# interface_dac_sma.net
KiCad netlist of a schematic drawn in EAGLE
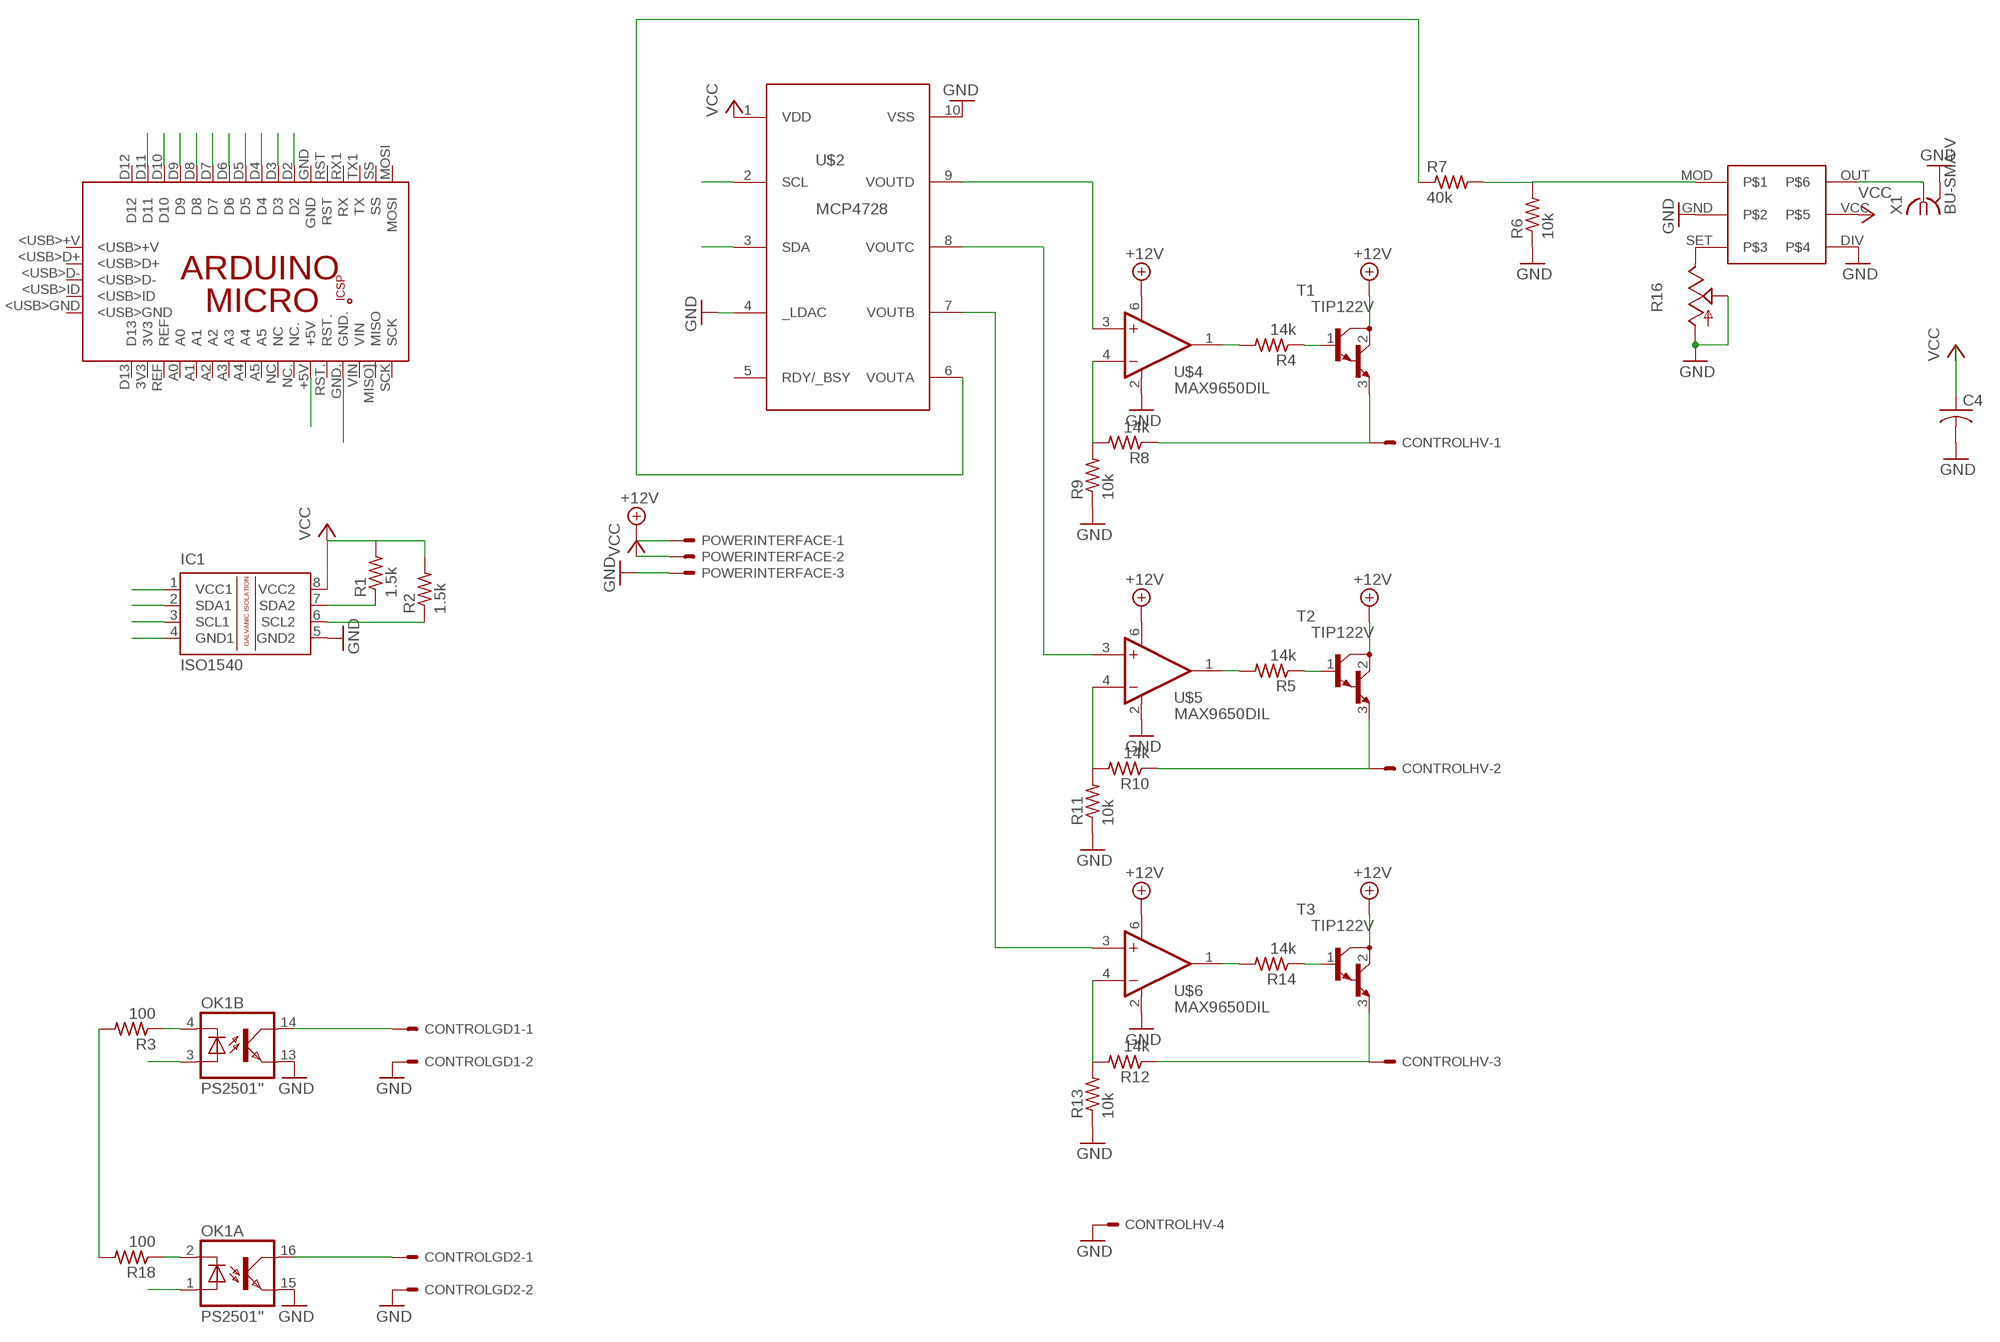
[diagram p0: schematic, sheet 1]

(export (version "E")
  (design (tool "Eeschema 10.0.6"))
  (components
    (comp (ref "C4")
      (value "C-US075-063X106")
      (footprint "eagle-import:C075-063X106")
      (libsource (lib "eagle-import") (part "C-US075-063X106"))
    )
    (comp (ref "CONTROLGD1")
      (value "KK-156-2")
      (footprint "eagle-import:KK-156-2")
      (libsource (lib "eagle-import") (part "KK-156-2"))
    )
    (comp (ref "CONTROLGD2")
      (value "KK-156-2")
      (footprint "eagle-import:KK-156-2")
      (libsource (lib "eagle-import") (part "KK-156-2"))
    )
    (comp (ref "CONTROLHV")
      (value "KK-156-4")
      (footprint "eagle-import:KK-156-4")
      (libsource (lib "eagle-import") (part "KK-156-4"))
    )
    (comp (ref "IC1")
      (value "ISO1540")
      (footprint "eagle-import:DIL08")
      (libsource (lib "eagle-import") (part "ISO1540"))
    )
    (comp (ref "OK1")
      (value "PS2501\"")
      (footprint "eagle-import:DIL16")
      (libsource (lib "eagle-import") (part "PS2501{dblquote}"))
    )
    (comp (ref "PCB1")
      (value "ARDUINO_MICRO")
      (footprint "eagle-import:ARDUINO_MICRO")
      (libsource (lib "eagle-import") (part "ARDUINO_MICRO"))
    )
    (comp (ref "POWERINTERFACE")
      (value "KK-156-3")
      (footprint "eagle-import:KK-156-3")
      (libsource (lib "eagle-import") (part "KK-156-3"))
    )
    (comp (ref "R1")
      (value "1.5k")
      (footprint "eagle-import:0207_12")
      (libsource (lib "eagle-import") (part "resistor_R-US_0207/12"))
    )
    (comp (ref "R2")
      (value "1.5k")
      (footprint "eagle-import:0207_12")
      (libsource (lib "eagle-import") (part "resistor_R-US_0207/12"))
    )
    (comp (ref "R3")
      (value "100")
      (footprint "eagle-import:0207_12")
      (libsource (lib "eagle-import") (part "R-US_0207/12"))
    )
    (comp (ref "R4")
      (value "14k")
      (footprint "eagle-import:0207_12")
      (libsource (lib "eagle-import") (part "resistor_R-US_0207/12"))
    )
    (comp (ref "R5")
      (value "14k")
      (footprint "eagle-import:0207_12")
      (libsource (lib "eagle-import") (part "resistor_R-US_0207/12"))
    )
    (comp (ref "R6")
      (value "10k")
      (footprint "eagle-import:0207_12")
      (libsource (lib "eagle-import") (part "resistor_R-US_0207/12"))
    )
    (comp (ref "R7")
      (value "40k")
      (footprint "eagle-import:0207_12")
      (libsource (lib "eagle-import") (part "resistor_R-US_0207/12"))
    )
    (comp (ref "R8")
      (value "14k")
      (footprint "eagle-import:0207_12")
      (libsource (lib "eagle-import") (part "resistor_R-US_0207/12"))
    )
    (comp (ref "R9")
      (value "10k")
      (footprint "eagle-import:0207_12")
      (libsource (lib "eagle-import") (part "resistor_R-US_0207/12"))
    )
    (comp (ref "R10")
      (value "14k")
      (footprint "eagle-import:0207_12")
      (libsource (lib "eagle-import") (part "resistor_R-US_0207/12"))
    )
    (comp (ref "R11")
      (value "10k")
      (footprint "eagle-import:0207_12")
      (libsource (lib "eagle-import") (part "resistor_R-US_0207/12"))
    )
    (comp (ref "R12")
      (value "14k")
      (footprint "eagle-import:0207_12")
      (libsource (lib "eagle-import") (part "resistor_R-US_0207/12"))
    )
    (comp (ref "R13")
      (value "10k")
      (footprint "eagle-import:0207_12")
      (libsource (lib "eagle-import") (part "resistor_R-US_0207/12"))
    )
    (comp (ref "R14")
      (value "14k")
      (footprint "eagle-import:0207_12")
      (libsource (lib "eagle-import") (part "resistor_R-US_0207/12"))
    )
    (comp (ref "R16")
      (value "TRIM_US-B90P")
      (footprint "eagle-import:SP19L")
      (libsource (lib "eagle-import") (part "TRIM_US-B90P"))
    )
    (comp (ref "R18")
      (value "100")
      (footprint "eagle-import:0207_12")
      (libsource (lib "eagle-import") (part "R-US_0207/12"))
    )
    (comp (ref "T1")
      (value "TIP122V")
      (footprint "eagle-import:TO220V")
      (libsource (lib "eagle-import") (part "TIP122V"))
    )
    (comp (ref "T2")
      (value "TIP122V")
      (footprint "eagle-import:TO220V")
      (libsource (lib "eagle-import") (part "TIP122V"))
    )
    (comp (ref "T3")
      (value "TIP122V")
      (footprint "eagle-import:TO220V")
      (libsource (lib "eagle-import") (part "TIP122V"))
    )
    (comp (ref "U$1")
      (value "LTC6992")
      (footprint "eagle-import:DIL06")
      (libsource (lib "eagle-import") (part "LTC6992"))
    )
    (comp (ref "U$2")
      (value "MCP4728DIL")
      (footprint "eagle-import:DIL10")
      (libsource (lib "eagle-import") (part "MCP4728DIL"))
    )
    (comp (ref "U$4")
      (value "MAX9650DIL")
      (footprint "eagle-import:DIL06-4")
      (libsource (lib "eagle-import") (part "MAX9650DIL"))
    )
    (comp (ref "U$5")
      (value "MAX9650DIL")
      (footprint "eagle-import:DIL06-4")
      (libsource (lib "eagle-import") (part "MAX9650DIL"))
    )
    (comp (ref "U$6")
      (value "MAX9650DIL")
      (footprint "eagle-import:DIL06-4")
      (libsource (lib "eagle-import") (part "MAX9650DIL"))
    )
    (comp (ref "X1")
      (value "BU-SMA-V")
      (footprint "eagle-import:BU-SMA-V")
      (libsource (lib "eagle-import") (part "BU-SMA-V"))
    )
  )
  (nets
    (net (code "1") (name "+12V") (class "Default")
      (node (ref "POWERINTERFACE") (pin "1") (pinfunction "S_1") (pintype "passive"))
      (node (ref "T1") (pin "2") (pinfunction "C_2") (pintype "passive"))
      (node (ref "T2") (pin "2") (pinfunction "C_2") (pintype "passive"))
      (node (ref "T3") (pin "2") (pinfunction "C_2") (pintype "passive"))
      (node (ref "U$4") (pin "6") (pinfunction "V+_6") (pintype "power_in"))
      (node (ref "U$5") (pin "6") (pinfunction "V+_6") (pintype "power_in"))
      (node (ref "U$6") (pin "6") (pinfunction "V+_6") (pintype "power_in"))
    )
    (net (code "2") (name "/A+5") (class "Default")
      (node (ref "IC1") (pin "1") (pinfunction "VCC1_1") (pintype "input"))
      (node (ref "PCB1") (pin "+5V") (pinfunction "+5V_+5V") (pintype "bidirectional"))
    )
    (net (code "3") (name "/AGND") (class "Default")
      (node (ref "IC1") (pin "4") (pinfunction "GND1_4") (pintype "input"))
      (node (ref "PCB1") (pin "GND.") (pinfunction "GND._GND.") (pintype "bidirectional"))
      (node (ref "R18") (pin "2") (pinfunction "2_2") (pintype "passive"))
      (node (ref "R3") (pin "2") (pinfunction "2_2") (pintype "passive"))
    )
    (net (code "4") (name "/N$2") (class "Default")
      (node (ref "R6") (pin "2") (pinfunction "2_2") (pintype "passive"))
      (node (ref "R7") (pin "2") (pinfunction "2_2") (pintype "passive"))
      (node (ref "U$1") (pin "MOD") (pinfunction "P$1_MOD") (pintype "bidirectional"))
    )
    (net (code "5") (name "/PWM6") (class "Default")
      (node (ref "OK1") (pin "3") (pinfunction "A_3") (pintype "passive"))
      (node (ref "PCB1") (pin "D6") (pinfunction "D6_D6") (pintype "bidirectional"))
    )
    (net (code "6") (name "/PWM9") (class "Default")
      (node (ref "OK1") (pin "1") (pinfunction "A_1") (pintype "passive"))
      (node (ref "PCB1") (pin "D9") (pinfunction "D9_D9") (pintype "bidirectional"))
    )
    (net (code "7") (name "/SCL") (class "Default")
      (node (ref "IC1") (pin "3") (pinfunction "SCL1_3") (pintype "input"))
      (node (ref "PCB1") (pin "D3") (pinfunction "D3_D3") (pintype "bidirectional"))
    )
    (net (code "8") (name "/SCL_OUT") (class "Default")
      (node (ref "IC1") (pin "6") (pinfunction "SCL2_6") (pintype "input"))
      (node (ref "R2") (pin "1") (pinfunction "1_1") (pintype "passive"))
      (node (ref "U$2") (pin "2") (pinfunction "SCL_2") (pintype "bidirectional"))
    )
    (net (code "9") (name "/SDA") (class "Default")
      (node (ref "IC1") (pin "2") (pinfunction "SDA1_2") (pintype "input"))
      (node (ref "PCB1") (pin "D2") (pinfunction "D2_D2") (pintype "bidirectional"))
    )
    (net (code "10") (name "/SDA_OUT") (class "Default")
      (node (ref "IC1") (pin "7") (pinfunction "SDA2_7") (pintype "input"))
      (node (ref "R1") (pin "1") (pinfunction "1_1") (pintype "passive"))
      (node (ref "U$2") (pin "3") (pinfunction "SDA_3") (pintype "bidirectional"))
    )
    (net (code "11") (name "GND") (class "Default")
      (node (ref "C4") (pin "2") (pinfunction "2_2") (pintype "passive"))
      (node (ref "CONTROLGD1") (pin "2") (pinfunction "S_2") (pintype "passive"))
      (node (ref "CONTROLGD2") (pin "2") (pinfunction "S_2") (pintype "passive"))
      (node (ref "CONTROLHV") (pin "4") (pinfunction "S_4") (pintype "passive"))
      (node (ref "IC1") (pin "5") (pinfunction "GND2_5") (pintype "input"))
      (node (ref "OK1") (pin "13") (pinfunction "EMI_13") (pintype "passive"))
      (node (ref "OK1") (pin "15") (pinfunction "EMI_15") (pintype "passive"))
      (node (ref "POWERINTERFACE") (pin "3") (pinfunction "S_3") (pintype "passive"))
      (node (ref "R11") (pin "1") (pinfunction "1_1") (pintype "passive"))
      (node (ref "R13") (pin "1") (pinfunction "1_1") (pintype "passive"))
      (node (ref "R16") (pin "A") (pinfunction "A_A") (pintype "passive"))
      (node (ref "R16") (pin "S") (pinfunction "S_S") (pintype "passive"))
      (node (ref "R6") (pin "1") (pinfunction "1_1") (pintype "passive"))
      (node (ref "R9") (pin "1") (pinfunction "1_1") (pintype "passive"))
      (node (ref "U$1") (pin "DIV") (pinfunction "P$4_DIV") (pintype "bidirectional"))
      (node (ref "U$1") (pin "GND") (pinfunction "P$2_GND") (pintype "bidirectional"))
      (node (ref "U$2") (pin "10") (pinfunction "VSS_10") (pintype "bidirectional"))
      (node (ref "U$2") (pin "4") (pinfunction "_LDAC_4") (pintype "bidirectional"))
      (node (ref "U$4") (pin "2") (pinfunction "V-_2") (pintype "power_in"))
      (node (ref "U$5") (pin "2") (pinfunction "V-_2") (pintype "power_in"))
      (node (ref "U$6") (pin "2") (pinfunction "V-_2") (pintype "power_in"))
      (node (ref "X1") (pin "2") (pinfunction "2_2") (pintype "passive"))
      (node (ref "X1") (pin "3") (pinfunction "2_3") (pintype "passive"))
      (node (ref "X1") (pin "4") (pinfunction "2_4") (pintype "passive"))
      (node (ref "X1") (pin "5") (pinfunction "2_5") (pintype "passive"))
    )
    (net (code "12") (name "Net-(CONTROLGD1A-S)") (class "Default")
      (node (ref "CONTROLGD1") (pin "1") (pinfunction "S_1") (pintype "passive"))
      (node (ref "OK1") (pin "14") (pinfunction "COL_14") (pintype "passive"))
    )
    (net (code "13") (name "Net-(CONTROLGD2A-S)") (class "Default")
      (node (ref "CONTROLGD2") (pin "1") (pinfunction "S_1") (pintype "passive"))
      (node (ref "OK1") (pin "16") (pinfunction "COL_16") (pintype "passive"))
    )
    (net (code "14") (name "Net-(CONTROLHVA-S)") (class "Default")
      (node (ref "CONTROLHV") (pin "1") (pinfunction "S_1") (pintype "passive"))
      (node (ref "R8") (pin "1") (pinfunction "1_1") (pintype "passive"))
      (node (ref "T1") (pin "3") (pinfunction "E_3") (pintype "passive"))
    )
    (net (code "15") (name "Net-(CONTROLHVB-S)") (class "Default")
      (node (ref "CONTROLHV") (pin "2") (pinfunction "S_2") (pintype "passive"))
      (node (ref "R10") (pin "1") (pinfunction "1_1") (pintype "passive"))
      (node (ref "T2") (pin "3") (pinfunction "E_3") (pintype "passive"))
    )
    (net (code "16") (name "Net-(CONTROLHVC-S)") (class "Default")
      (node (ref "CONTROLHV") (pin "3") (pinfunction "S_3") (pintype "passive"))
      (node (ref "R12") (pin "1") (pinfunction "1_1") (pintype "passive"))
      (node (ref "T3") (pin "3") (pinfunction "E_3") (pintype "passive"))
    )
    (net (code "17") (name "Net-(OK1A-C)") (class "Default")
      (node (ref "OK1") (pin "2") (pinfunction "C_2") (pintype "passive"))
      (node (ref "R18") (pin "1") (pinfunction "1_1") (pintype "passive"))
    )
    (net (code "18") (name "Net-(OK1B-C)") (class "Default")
      (node (ref "OK1") (pin "4") (pinfunction "C_4") (pintype "passive"))
      (node (ref "R3") (pin "1") (pinfunction "1_1") (pintype "passive"))
    )
    (net (code "19") (name "Net-(T1-B)") (class "Default")
      (node (ref "R4") (pin "1") (pinfunction "1_1") (pintype "passive"))
      (node (ref "T1") (pin "1") (pinfunction "B_1") (pintype "passive"))
    )
    (net (code "20") (name "Net-(T2-B)") (class "Default")
      (node (ref "R5") (pin "1") (pinfunction "1_1") (pintype "passive"))
      (node (ref "T2") (pin "1") (pinfunction "B_1") (pintype "passive"))
    )
    (net (code "21") (name "Net-(T3-B)") (class "Default")
      (node (ref "R14") (pin "1") (pinfunction "1_1") (pintype "passive"))
      (node (ref "T3") (pin "1") (pinfunction "B_1") (pintype "passive"))
    )
    (net (code "22") (name "Net-(U$1-P$3)") (class "Default")
      (node (ref "R16") (pin "E") (pinfunction "E_E") (pintype "passive"))
      (node (ref "U$1") (pin "SET") (pinfunction "P$3_SET") (pintype "bidirectional"))
    )
    (net (code "23") (name "Net-(U$1-P$6)") (class "Default")
      (node (ref "U$1") (pin "OUT") (pinfunction "P$6_OUT") (pintype "bidirectional"))
      (node (ref "X1") (pin "1") (pinfunction "1_1") (pintype "passive"))
    )
    (net (code "24") (name "Net-(U$2-VOUTA)") (class "Default")
      (node (ref "R7") (pin "1") (pinfunction "1_1") (pintype "passive"))
      (node (ref "U$2") (pin "6") (pinfunction "VOUTA_6") (pintype "bidirectional"))
    )
    (net (code "25") (name "Net-(U$2-VOUTB)") (class "Default")
      (node (ref "U$2") (pin "7") (pinfunction "VOUTB_7") (pintype "bidirectional"))
      (node (ref "U$6") (pin "3") (pinfunction "+IN_3") (pintype "input"))
    )
    (net (code "26") (name "Net-(U$2-VOUTC)") (class "Default")
      (node (ref "U$2") (pin "8") (pinfunction "VOUTC_8") (pintype "bidirectional"))
      (node (ref "U$5") (pin "3") (pinfunction "+IN_3") (pintype "input"))
    )
    (net (code "27") (name "Net-(U$2-VOUTD)") (class "Default")
      (node (ref "U$2") (pin "9") (pinfunction "VOUTD_9") (pintype "bidirectional"))
      (node (ref "U$4") (pin "3") (pinfunction "+IN_3") (pintype "input"))
    )
    (net (code "28") (name "Net-(U$4--IN)") (class "Default")
      (node (ref "R8") (pin "2") (pinfunction "2_2") (pintype "passive"))
      (node (ref "R9") (pin "2") (pinfunction "2_2") (pintype "passive"))
      (node (ref "U$4") (pin "4") (pinfunction "-IN_4") (pintype "input"))
    )
    (net (code "29") (name "Net-(U$4-OUT)") (class "Default")
      (node (ref "R4") (pin "2") (pinfunction "2_2") (pintype "passive"))
      (node (ref "U$4") (pin "1") (pinfunction "OUT_1") (pintype "output"))
    )
    (net (code "30") (name "Net-(U$5--IN)") (class "Default")
      (node (ref "R10") (pin "2") (pinfunction "2_2") (pintype "passive"))
      (node (ref "R11") (pin "2") (pinfunction "2_2") (pintype "passive"))
      (node (ref "U$5") (pin "4") (pinfunction "-IN_4") (pintype "input"))
    )
    (net (code "31") (name "Net-(U$5-OUT)") (class "Default")
      (node (ref "R5") (pin "2") (pinfunction "2_2") (pintype "passive"))
      (node (ref "U$5") (pin "1") (pinfunction "OUT_1") (pintype "output"))
    )
    (net (code "32") (name "Net-(U$6--IN)") (class "Default")
      (node (ref "R12") (pin "2") (pinfunction "2_2") (pintype "passive"))
      (node (ref "R13") (pin "2") (pinfunction "2_2") (pintype "passive"))
      (node (ref "U$6") (pin "4") (pinfunction "-IN_4") (pintype "input"))
    )
    (net (code "33") (name "Net-(U$6-OUT)") (class "Default")
      (node (ref "R14") (pin "2") (pinfunction "2_2") (pintype "passive"))
      (node (ref "U$6") (pin "1") (pinfunction "OUT_1") (pintype "output"))
    )
    (net (code "34") (name "VCC") (class "Default")
      (node (ref "C4") (pin "1") (pinfunction "1_1") (pintype "passive"))
      (node (ref "IC1") (pin "8") (pinfunction "VCC2_8") (pintype "input"))
      (node (ref "POWERINTERFACE") (pin "2") (pinfunction "S_2") (pintype "passive"))
      (node (ref "R1") (pin "2") (pinfunction "2_2") (pintype "passive"))
      (node (ref "R2") (pin "2") (pinfunction "2_2") (pintype "passive"))
      (node (ref "U$1") (pin "VCC") (pinfunction "P$5_VCC") (pintype "bidirectional"))
      (node (ref "U$2") (pin "1") (pinfunction "VDD_1") (pintype "bidirectional"))
    )
    (net (code "35") (name "unconnected-(PCB1-MISO-PadMISO])") (class "Default")
      (node (ref "PCB1") (pin "MISO]") (pinfunction "MISO_MISO]") (pintype "bidirectional"))
    )
    (net (code "36") (name "unconnected-(PCB1-Pad3V3)") (class "Default")
      (node (ref "PCB1") (pin "3V3") (pinfunction "3V3_3V3") (pintype "bidirectional"))
    )
    (net (code "37") (name "unconnected-(PCB1-Pad5V)") (class "Default")
      (node (ref "PCB1") (pin "5V") (pinfunction "5V_5V") (pintype "bidirectional"))
    )
    (net (code "38") (name "unconnected-(PCB1-Pad<USB>+V)") (class "Default")
      (node (ref "PCB1") (pin "<USB>+V") (pinfunction "<USB>+V_<USB>+V") (pintype "bidirectional"))
    )
    (net (code "39") (name "unconnected-(PCB1-Pad<USB>D+)") (class "Default")
      (node (ref "PCB1") (pin "<USB>D+") (pinfunction "<USB>D+_<USB>D+") (pintype "bidirectional"))
    )
    (net (code "40") (name "unconnected-(PCB1-Pad<USB>D-)") (class "Default")
      (node (ref "PCB1") (pin "<USB>D-") (pinfunction "<USB>D-_<USB>D-") (pintype "bidirectional"))
    )
    (net (code "41") (name "unconnected-(PCB1-Pad<USB>GND)") (class "Default")
      (node (ref "PCB1") (pin "<USB>GND") (pinfunction "<USB>GND_<USB>GND") (pintype "bidirectional"))
    )
    (net (code "42") (name "unconnected-(PCB1-Pad<USB>ID)") (class "Default")
      (node (ref "PCB1") (pin "<USB>ID") (pinfunction "<USB>ID_<USB>ID") (pintype "bidirectional"))
    )
    (net (code "43") (name "unconnected-(PCB1-PadA0)") (class "Default")
      (node (ref "PCB1") (pin "A0") (pinfunction "A0_A0") (pintype "bidirectional"))
    )
    (net (code "44") (name "unconnected-(PCB1-PadA1)") (class "Default")
      (node (ref "PCB1") (pin "A1") (pinfunction "A1_A1") (pintype "bidirectional"))
    )
    (net (code "45") (name "unconnected-(PCB1-PadA2)") (class "Default")
      (node (ref "PCB1") (pin "A2") (pinfunction "A2_A2") (pintype "bidirectional"))
    )
    (net (code "46") (name "unconnected-(PCB1-PadA3)") (class "Default")
      (node (ref "PCB1") (pin "A3") (pinfunction "A3_A3") (pintype "bidirectional"))
    )
    (net (code "47") (name "unconnected-(PCB1-PadA4)") (class "Default")
      (node (ref "PCB1") (pin "A4") (pinfunction "A4_A4") (pintype "bidirectional"))
    )
    (net (code "48") (name "unconnected-(PCB1-PadA5)") (class "Default")
      (node (ref "PCB1") (pin "A5") (pinfunction "A5_A5") (pintype "bidirectional"))
    )
    (net (code "49") (name "unconnected-(PCB1-PadD4)") (class "Default")
      (node (ref "PCB1") (pin "D4") (pinfunction "D4_D4") (pintype "bidirectional"))
    )
    (net (code "50") (name "unconnected-(PCB1-PadD5)") (class "Default")
      (node (ref "PCB1") (pin "D5") (pinfunction "D5_D5") (pintype "bidirectional"))
    )
    (net (code "51") (name "unconnected-(PCB1-PadD7)") (class "Default")
      (node (ref "PCB1") (pin "D7") (pinfunction "D7_D7") (pintype "bidirectional"))
    )
    (net (code "52") (name "unconnected-(PCB1-PadD8)") (class "Default")
      (node (ref "PCB1") (pin "D8") (pinfunction "D8_D8") (pintype "bidirectional"))
    )
    (net (code "53") (name "unconnected-(PCB1-PadD10)") (class "Default")
      (node (ref "PCB1") (pin "D10") (pinfunction "D10_D10") (pintype "bidirectional"))
    )
    (net (code "54") (name "unconnected-(PCB1-PadD11)") (class "Default")
      (node (ref "PCB1") (pin "D11") (pinfunction "D11_D11") (pintype "bidirectional"))
    )
    (net (code "55") (name "unconnected-(PCB1-PadD12)") (class "Default")
      (node (ref "PCB1") (pin "D12") (pinfunction "D12_D12") (pintype "bidirectional"))
    )
    (net (code "56") (name "unconnected-(PCB1-PadD13)") (class "Default")
      (node (ref "PCB1") (pin "D13") (pinfunction "D13_D13") (pintype "bidirectional"))
    )
    (net (code "57") (name "unconnected-(PCB1-PadGND)") (class "Default")
      (node (ref "PCB1") (pin "GND") (pinfunction "GND_GND") (pintype "bidirectional"))
    )
    (net (code "58") (name "unconnected-(PCB1-PadGND_)") (class "Default")
      (node (ref "PCB1") (pin "GND_") (pinfunction "GND__GND_") (pintype "bidirectional"))
    )
    (net (code "59") (name "unconnected-(PCB1-PadMISO.)") (class "Default")
      (node (ref "PCB1") (pin "MISO.") (pinfunction "MISO._MISO.") (pintype "bidirectional"))
    )
    (net (code "60") (name "unconnected-(PCB1-PadMOSI)") (class "Default")
      (node (ref "PCB1") (pin "MOSI") (pinfunction "MOSI_MOSI") (pintype "bidirectional"))
    )
    (net (code "61") (name "unconnected-(PCB1-PadMOSI.)") (class "Default")
      (node (ref "PCB1") (pin "MOSI.") (pinfunction "MOSI._MOSI.") (pintype "bidirectional"))
    )
    (net (code "62") (name "unconnected-(PCB1-PadNC)") (class "Default")
      (node (ref "PCB1") (pin "NC") (pinfunction "NC_NC") (pintype "bidirectional"))
    )
    (net (code "63") (name "unconnected-(PCB1-PadNC.)") (class "Default")
      (node (ref "PCB1") (pin "NC.") (pinfunction "NC._NC.") (pintype "bidirectional"))
    )
    (net (code "64") (name "unconnected-(PCB1-PadREF)") (class "Default")
      (node (ref "PCB1") (pin "REF") (pinfunction "REF_REF") (pintype "bidirectional"))
    )
    (net (code "65") (name "unconnected-(PCB1-PadRESET..)") (class "Default")
      (node (ref "PCB1") (pin "RESET..") (pinfunction "RESET.._RESET..") (pintype "bidirectional"))
    )
    (net (code "66") (name "unconnected-(PCB1-PadRST)") (class "Default")
      (node (ref "PCB1") (pin "RST") (pinfunction "RST_RST") (pintype "bidirectional"))
    )
    (net (code "67") (name "unconnected-(PCB1-PadRST.)") (class "Default")
      (node (ref "PCB1") (pin "RST.") (pinfunction "RST._RST.") (pintype "bidirectional"))
    )
    (net (code "68") (name "unconnected-(PCB1-PadSCK)") (class "Default")
      (node (ref "PCB1") (pin "SCK") (pinfunction "SCK_SCK") (pintype "bidirectional"))
    )
    (net (code "69") (name "unconnected-(PCB1-PadSCK.)") (class "Default")
      (node (ref "PCB1") (pin "SCK.") (pinfunction "SCK._SCK.") (pintype "bidirectional"))
    )
    (net (code "70") (name "unconnected-(PCB1-PadSS)") (class "Default")
      (node (ref "PCB1") (pin "SS") (pinfunction "SS_SS") (pintype "bidirectional"))
    )
    (net (code "71") (name "unconnected-(PCB1-PadVIN)") (class "Default")
      (node (ref "PCB1") (pin "VIN") (pinfunction "VIN_VIN") (pintype "bidirectional"))
    )
    (net (code "72") (name "unconnected-(PCB1-RX-PadRX1)") (class "Default")
      (node (ref "PCB1") (pin "RX1") (pinfunction "RX_RX1") (pintype "bidirectional"))
    )
    (net (code "73") (name "unconnected-(PCB1-TX-PadTX1)") (class "Default")
      (node (ref "PCB1") (pin "TX1") (pinfunction "TX_TX1") (pintype "bidirectional"))
    )
    (net (code "74") (name "unconnected-(U$2-RDY{slash}_BSY-Pad5)") (class "Default")
      (node (ref "U$2") (pin "5") (pinfunction "RDY/_BSY_5") (pintype "bidirectional"))
    )
  )
)
